# hid_detector.net
KiCad netlist of a schematic drawn in EAGLE
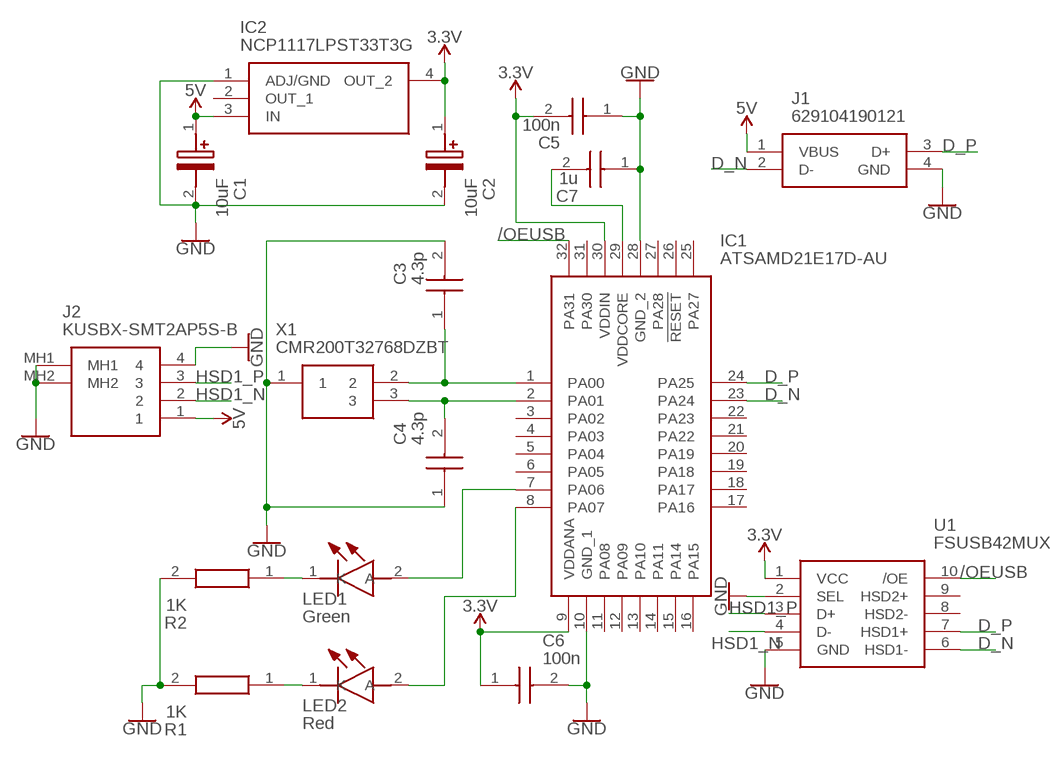
[diagram p0: schematic, sheet 1]

(export (version "E")
  (design (tool "Eeschema 10.0.6"))
  (components
    (comp (ref "C1")
      (value "10uF")
      (footprint "eagle-import:CAPAE400X550N")
      (fields
        (field (name "MANUFACTURER_PART_NUMBER") "865080440002")
        (field (name "MOUSER_PART_NUMBER") "710-865080440002")
      )
      (libsource (lib "eagle-import") (part "865080440002"))
    )
    (comp (ref "C2")
      (value "10uF")
      (footprint "eagle-import:CAPAE400X550N")
      (fields
        (field (name "MANUFACTURER_PART_NUMBER") "865080440002")
        (field (name "MOUSER_PART_NUMBER") "710-865080440002")
      )
      (libsource (lib "eagle-import") (part "865080440002"))
    )
    (comp (ref "C3")
      (value "4.3p")
      (footprint "eagle-import:CAPC0603X33N")
      (fields (field (name "MANUFACTURER_PART_NUMBER") "GRM0335C1E4R3WA01D"))
      (libsource (lib "eagle-import") (part "GRM0335C1E4R3WA01D"))
    )
    (comp (ref "C4")
      (value "4.3p")
      (footprint "eagle-import:CAPC0603X33N")
      (fields (field (name "MANUFACTURER_PART_NUMBER") "GRM0335C1E4R3WA01D"))
      (libsource (lib "eagle-import") (part "GRM0335C1E4R3WA01D"))
    )
    (comp (ref "C5")
      (value "100n")
      (footprint "eagle-import:CAPC1005X55N")
      (fields
        (field (name "MANUFACTURER_PART_NUMBER") "EMF105B7104MVHF")
        (field (name "MOUSER_PART_NUMBER") "963-EMF105B7104MVHF")
      )
      (libsource (lib "eagle-import") (part "EMF105B7104MVHF"))
    )
    (comp (ref "C6")
      (value "100n")
      (footprint "eagle-import:CAPC1005X55N")
      (fields
        (field (name "MANUFACTURER_PART_NUMBER") "EMF105B7104MVHF")
        (field (name "MOUSER_PART_NUMBER") "963-EMF105B7104MVHF")
      )
      (libsource (lib "eagle-import") (part "EMF105B7104MVHF"))
    )
    (comp (ref "C7")
      (value "1u")
      (footprint "eagle-import:CAPC1005X55N")
      (fields
        (field (name "MANUFACTURER_PART_NUMBER") "EMK105BJ105MVHF")
        (field (name "MOUSER_PART_NUMBER") "963-EMK105BJ105MVHF")
      )
      (libsource (lib "eagle-import") (part "EMK105BJ105MVHF"))
    )
    (comp (ref "IC1")
      (value "ATSAMD21E17D-AU")
      (footprint "eagle-import:QFP80P900X900X120-32N")
      (fields (field (name "MOUSER_PART_NUMBER") "556-ATSAMD21E17D-AU"))
      (libsource (lib "eagle-import") (part "ATSAMD21E17D-AU"))
    )
    (comp (ref "IC2")
      (value "NCP1117LPST33T3G")
      (footprint "eagle-import:SOT230P700X180-4N")
      (fields (field (name "MOUSER_PART_NUMBER") "863-NCP1117LPST33T3G"))
      (libsource (lib "eagle-import") (part "NCP1117LPST33T3G"))
    )
    (comp (ref "J1")
      (value "629104190121")
      (footprint "eagle-import:629104190121")
      (fields (field (name "MOUSER_PART_NUMBER") "710-629104190121"))
      (libsource (lib "eagle-import") (part "629104190121"))
    )
    (comp (ref "J2")
      (value "KUSBX-SMT2AP5S-B")
      (footprint "eagle-import:KUSBXSMT2AP5SB")
      (fields (field (name "MOUSER_PART_NUMBER") "806-KUSBXSMT2AP5SB"))
      (libsource (lib "eagle-import") (part "KUSBX-SMT2AP5S-B"))
    )
    (comp (ref "LED1")
      (value "Green")
      (footprint "eagle-import:LEDC3215X130N")
      (fields
        (field (name "MANUFACTURER_PART_NUMBER") "CMD15-21VGD/TR8")
        (field (name "MOUSER_PART_NUMBER") "606-CMD15-21VGD/TR8")
      )
      (libsource (lib "eagle-import") (part "CMD15-21VGD_TR8"))
    )
    (comp (ref "LED2")
      (value "Red")
      (footprint "eagle-import:LEDC1608X85N")
      (fields
        (field (name "MANUFACTURER_PART_NUMBER") "APT1608EC")
        (field (name "MOUSER_PART_NUMBER") "604-APT1608EC")
      )
      (libsource (lib "eagle-import") (part "APT1608EC"))
    )
    (comp (ref "R1")
      (value "1K")
      (footprint "eagle-import:RESC1005X40N")
      (fields
        (field (name "MANUFACTURER_PART_NUMBER") "RK73H1ETTP1001F")
        (field (name "MOUSER_PART_NUMBER") "660-RK73H1ETTP1001F")
      )
      (libsource (lib "eagle-import") (part "RK73H1ETTP1001F"))
    )
    (comp (ref "R2")
      (value "1K")
      (footprint "eagle-import:RESC1005X40N")
      (fields
        (field (name "MANUFACTURER_PART_NUMBER") "RK73H1ETTP1001F")
        (field (name "MOUSER_PART_NUMBER") "660-RK73H1ETTP1001F")
      )
      (libsource (lib "eagle-import") (part "RK73H1ETTP1001F"))
    )
    (comp (ref "U1")
      (value "FSUSB42MUX")
      (footprint "eagle-import:SOP50P490X110-10N")
      (fields (field (name "MOUSER_PART_NUMBER") "512-FSUSB42MUX"))
      (libsource (lib "eagle-import") (part "FSUSB42MUX"))
    )
    (comp (ref "X1")
      (value "CMR200T32768DZBT")
      (footprint "eagle-import:CMR200T")
      (fields (field (name "MOUSER_PART_NUMBER") "695-CMR200T32768DZBT"))
      (libsource (lib "eagle-import") (part "CMR200T32768DZBT"))
    )
  )
  (nets
    (net (code "1") (name "/D_N") (class "Default")
      (node (ref "IC1") (pin "23") (pinfunction "PA24_23") (pintype "bidirectional"))
      (node (ref "J1") (pin "2") (pinfunction "D-_2") (pintype "bidirectional"))
      (node (ref "U1") (pin "6") (pinfunction "HSD1-_6") (pintype "bidirectional"))
    )
    (net (code "2") (name "/D_P") (class "Default")
      (node (ref "IC1") (pin "24") (pinfunction "PA25_24") (pintype "bidirectional"))
      (node (ref "J1") (pin "3") (pinfunction "D+_3") (pintype "bidirectional"))
      (node (ref "U1") (pin "7") (pinfunction "HSD1+_7") (pintype "power_in"))
    )
    (net (code "3") (name "/HSD1_N") (class "Default")
      (node (ref "J2") (pin "2") (pinfunction "2_2") (pintype "bidirectional"))
      (node (ref "U1") (pin "4") (pinfunction "D-_4") (pintype "bidirectional"))
    )
    (net (code "4") (name "/HSD1_P") (class "Default")
      (node (ref "J2") (pin "3") (pinfunction "3_3") (pintype "bidirectional"))
      (node (ref "U1") (pin "3") (pinfunction "D+_3") (pintype "bidirectional"))
    )
    (net (code "5") (name "/{slash}OEUSB") (class "Default")
      (node (ref "IC1") (pin "32") (pinfunction "PA31_32") (pintype "bidirectional"))
      (node (ref "U1") (pin "10") (pinfunction "/OE_10") (pintype "bidirectional"))
    )
    (net (code "6") (name "3.3V") (class "Default")
      (node (ref "C2") (pin "1") (pinfunction "+_1") (pintype "bidirectional"))
      (node (ref "C5") (pin "2") (pinfunction "2_2") (pintype "bidirectional"))
      (node (ref "C6") (pin "1") (pinfunction "1_1") (pintype "bidirectional"))
      (node (ref "IC1") (pin "30") (pinfunction "VDDIN_30") (pintype "bidirectional"))
      (node (ref "IC1") (pin "9") (pinfunction "VDDANA_9") (pintype "bidirectional"))
      (node (ref "IC2") (pin "4") (pinfunction "OUT_2_4") (pintype "output"))
      (node (ref "U1") (pin "1") (pinfunction "VCC_1") (pintype "bidirectional"))
    )
    (net (code "7") (name "5V") (class "Default")
      (node (ref "C1") (pin "1") (pinfunction "+_1") (pintype "bidirectional"))
      (node (ref "IC2") (pin "3") (pinfunction "IN_3") (pintype "input"))
      (node (ref "J1") (pin "1") (pinfunction "VBUS_1") (pintype "bidirectional"))
      (node (ref "J2") (pin "1") (pinfunction "1_1") (pintype "bidirectional"))
    )
    (net (code "8") (name "GND") (class "Default")
      (node (ref "C1") (pin "2") (pinfunction "-_2") (pintype "bidirectional"))
      (node (ref "C2") (pin "2") (pinfunction "-_2") (pintype "bidirectional"))
      (node (ref "C3") (pin "2") (pinfunction "2_2") (pintype "bidirectional"))
      (node (ref "C4") (pin "1") (pinfunction "1_1") (pintype "bidirectional"))
      (node (ref "C5") (pin "1") (pinfunction "1_1") (pintype "bidirectional"))
      (node (ref "C6") (pin "2") (pinfunction "2_2") (pintype "bidirectional"))
      (node (ref "C7") (pin "1") (pinfunction "1_1") (pintype "bidirectional"))
      (node (ref "IC1") (pin "10") (pinfunction "GND_1_10") (pintype "bidirectional"))
      (node (ref "IC1") (pin "28") (pinfunction "GND_2_28") (pintype "bidirectional"))
      (node (ref "IC2") (pin "1") (pinfunction "ADJ/GND_1") (pintype "power_in"))
      (node (ref "J1") (pin "4") (pinfunction "GND_4") (pintype "bidirectional"))
      (node (ref "J2") (pin "4") (pinfunction "4_4") (pintype "bidirectional"))
      (node (ref "J2") (pin "MH1") (pinfunction "MH1_MH1") (pintype "bidirectional"))
      (node (ref "J2") (pin "MH2") (pinfunction "MH2_MH2") (pintype "bidirectional"))
      (node (ref "R1") (pin "2") (pinfunction "2_2") (pintype "bidirectional"))
      (node (ref "R2") (pin "2") (pinfunction "2_2") (pintype "bidirectional"))
      (node (ref "U1") (pin "2") (pinfunction "SEL_2") (pintype "bidirectional"))
      (node (ref "U1") (pin "5") (pinfunction "GND_5") (pintype "bidirectional"))
      (node (ref "X1") (pin "1") (pinfunction "1_1") (pintype "bidirectional"))
    )
    (net (code "9") (name "Net-(IC1-PA00)") (class "Default")
      (node (ref "C3") (pin "1") (pinfunction "1_1") (pintype "bidirectional"))
      (node (ref "IC1") (pin "1") (pinfunction "PA00_1") (pintype "bidirectional"))
      (node (ref "X1") (pin "2") (pinfunction "2_2") (pintype "bidirectional"))
    )
    (net (code "10") (name "Net-(IC1-PA01)") (class "Default")
      (node (ref "C4") (pin "2") (pinfunction "2_2") (pintype "bidirectional"))
      (node (ref "IC1") (pin "2") (pinfunction "PA01_2") (pintype "bidirectional"))
      (node (ref "X1") (pin "3") (pinfunction "3_3") (pintype "bidirectional"))
    )
    (net (code "11") (name "Net-(IC1-PA06)") (class "Default")
      (node (ref "IC1") (pin "7") (pinfunction "PA06_7") (pintype "bidirectional"))
      (node (ref "LED1") (pin "2") (pinfunction "A_2") (pintype "bidirectional"))
    )
    (net (code "12") (name "Net-(IC1-PA07)") (class "Default")
      (node (ref "IC1") (pin "8") (pinfunction "PA07_8") (pintype "bidirectional"))
      (node (ref "LED2") (pin "2") (pinfunction "A_2") (pintype "bidirectional"))
    )
    (net (code "13") (name "Net-(IC1-VDDCORE)") (class "Default")
      (node (ref "C7") (pin "2") (pinfunction "2_2") (pintype "bidirectional"))
      (node (ref "IC1") (pin "29") (pinfunction "VDDCORE_29") (pintype "bidirectional"))
    )
    (net (code "14") (name "Net-(LED1-K)") (class "Default")
      (node (ref "LED1") (pin "1") (pinfunction "K_1") (pintype "bidirectional"))
      (node (ref "R2") (pin "1") (pinfunction "1_1") (pintype "bidirectional"))
    )
    (net (code "15") (name "Net-(LED2-K)") (class "Default")
      (node (ref "LED2") (pin "1") (pinfunction "K_1") (pintype "bidirectional"))
      (node (ref "R1") (pin "1") (pinfunction "1_1") (pintype "bidirectional"))
    )
    (net (code "16") (name "unconnected-(IC1-PA02-Pad3)") (class "Default")
      (node (ref "IC1") (pin "3") (pinfunction "PA02_3") (pintype "bidirectional"))
    )
    (net (code "17") (name "unconnected-(IC1-PA03-Pad4)") (class "Default")
      (node (ref "IC1") (pin "4") (pinfunction "PA03_4") (pintype "bidirectional"))
    )
    (net (code "18") (name "unconnected-(IC1-PA04-Pad5)") (class "Default")
      (node (ref "IC1") (pin "5") (pinfunction "PA04_5") (pintype "bidirectional"))
    )
    (net (code "19") (name "unconnected-(IC1-PA05-Pad6)") (class "Default")
      (node (ref "IC1") (pin "6") (pinfunction "PA05_6") (pintype "bidirectional"))
    )
    (net (code "20") (name "unconnected-(IC1-PA08-Pad11)") (class "Default")
      (node (ref "IC1") (pin "11") (pinfunction "PA08_11") (pintype "bidirectional"))
    )
    (net (code "21") (name "unconnected-(IC1-PA09-Pad12)") (class "Default")
      (node (ref "IC1") (pin "12") (pinfunction "PA09_12") (pintype "bidirectional"))
    )
    (net (code "22") (name "unconnected-(IC1-PA10-Pad13)") (class "Default")
      (node (ref "IC1") (pin "13") (pinfunction "PA10_13") (pintype "bidirectional"))
    )
    (net (code "23") (name "unconnected-(IC1-PA11-Pad14)") (class "Default")
      (node (ref "IC1") (pin "14") (pinfunction "PA11_14") (pintype "bidirectional"))
    )
    (net (code "24") (name "unconnected-(IC1-PA14-Pad15)") (class "Default")
      (node (ref "IC1") (pin "15") (pinfunction "PA14_15") (pintype "bidirectional"))
    )
    (net (code "25") (name "unconnected-(IC1-PA15-Pad16)") (class "Default")
      (node (ref "IC1") (pin "16") (pinfunction "PA15_16") (pintype "bidirectional"))
    )
    (net (code "26") (name "unconnected-(IC1-PA16-Pad17)") (class "Default")
      (node (ref "IC1") (pin "17") (pinfunction "PA16_17") (pintype "bidirectional"))
    )
    (net (code "27") (name "unconnected-(IC1-PA17-Pad18)") (class "Default")
      (node (ref "IC1") (pin "18") (pinfunction "PA17_18") (pintype "bidirectional"))
    )
    (net (code "28") (name "unconnected-(IC1-PA18-Pad19)") (class "Default")
      (node (ref "IC1") (pin "19") (pinfunction "PA18_19") (pintype "bidirectional"))
    )
    (net (code "29") (name "unconnected-(IC1-PA19-Pad20)") (class "Default")
      (node (ref "IC1") (pin "20") (pinfunction "PA19_20") (pintype "bidirectional"))
    )
    (net (code "30") (name "unconnected-(IC1-PA22-Pad21)") (class "Default")
      (node (ref "IC1") (pin "21") (pinfunction "PA22_21") (pintype "bidirectional"))
    )
    (net (code "31") (name "unconnected-(IC1-PA23-Pad22)") (class "Default")
      (node (ref "IC1") (pin "22") (pinfunction "PA23_22") (pintype "bidirectional"))
    )
    (net (code "32") (name "unconnected-(IC1-PA27-Pad25)") (class "Default")
      (node (ref "IC1") (pin "25") (pinfunction "PA27_25") (pintype "bidirectional"))
    )
    (net (code "33") (name "unconnected-(IC1-PA28-Pad27)") (class "Default")
      (node (ref "IC1") (pin "27") (pinfunction "PA28_27") (pintype "bidirectional"))
    )
    (net (code "34") (name "unconnected-(IC1-PA30-Pad31)") (class "Default")
      (node (ref "IC1") (pin "31") (pinfunction "PA30_31") (pintype "bidirectional"))
    )
    (net (code "35") (name "unconnected-(IC1-~{RESET}-Pad26)") (class "Default")
      (node (ref "IC1") (pin "26") (pinfunction "~{RESET}_26") (pintype "bidirectional"))
    )
    (net (code "36") (name "unconnected-(IC2-OUT_1-Pad2)") (class "Default")
      (node (ref "IC2") (pin "2") (pinfunction "OUT_1_2") (pintype "output"))
    )
    (net (code "37") (name "unconnected-(U1-HSD2+-Pad9)") (class "Default")
      (node (ref "U1") (pin "9") (pinfunction "HSD2+_9") (pintype "bidirectional"))
    )
    (net (code "38") (name "unconnected-(U1-HSD2--Pad8)") (class "Default")
      (node (ref "U1") (pin "8") (pinfunction "HSD2-_8") (pintype "bidirectional"))
    )
  )
)
